# Battery-Management.net
KiCad netlist of a schematic drawn in Altium Designer
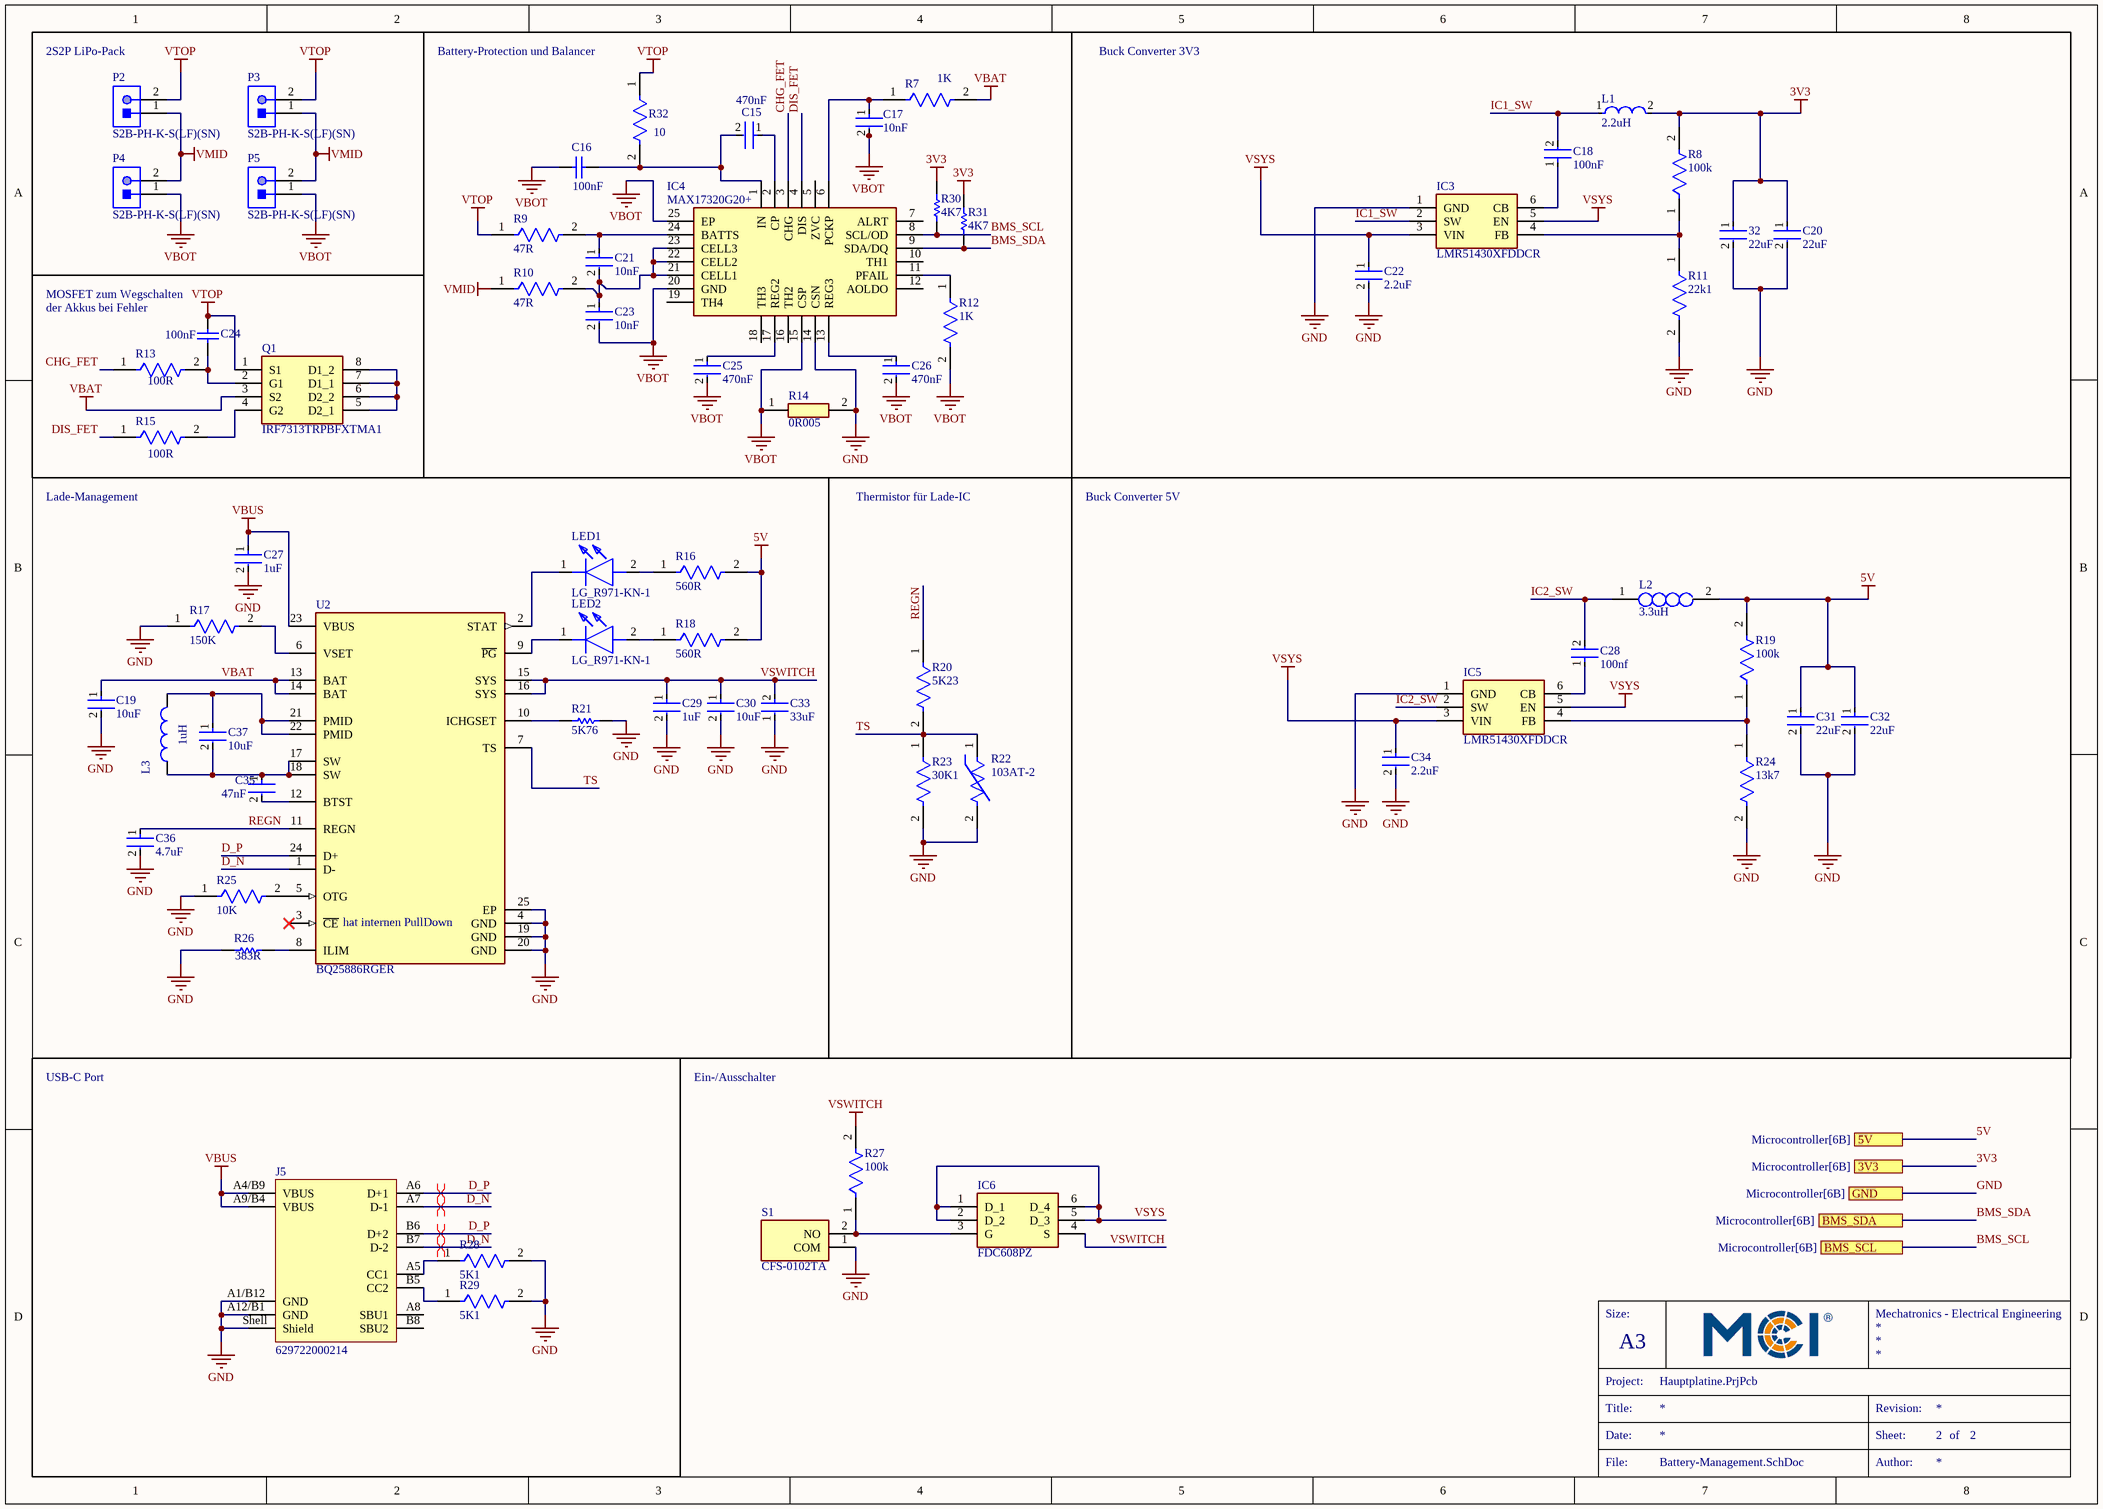
[diagram p0: Battery-Management.SchDoc]

(export (version "E")
  (design (tool "Eeschema 10.0.6"))
  (components
    (comp (ref "32")
      (value "22uF")
      (footprint "FP-C1210C226K4RACTU-MFG")
      (description "CAP CER 22UF 16V X7R 1210")
      (fields (field (name "VOLTAGE") "16V") (field (name "TOLERANCE") "10%"))
      (libsource (lib "Altium Content Vault") (part "b4654b650e69147ec39a6b967a45e02"))
    )
    (comp (ref "C15")
      (value "470nF")
      (footprint "FP-C0805C-DN-MFG")
      (description "CAP CER 0.47UF 25V X7R 0805")
      (fields (field (name "MANUFACTURER") "KEMET") (field (name "TOLERANCE") "0.05"))
      (libsource (lib "Altium Content Vault") (part "b4654b650e69147ec39a6b967a45e02"))
    )
    (comp (ref "C16")
      (value "100nF")
      (footprint "CAPC2013X145X50LL20T20")
      (fields (field (name "PART NUMBER") "VJ0805Y104JXXPW1BC") (field (name "MANUFACTURER") "Vitramon"))
      (libsource (lib "Altium Content Vault") (part "CAP"))
    )
    (comp (ref "C17")
      (value "10nF")
      (footprint "FP-AC0805-0_85-MFG")
      (description "AC Series 0805 10 nF 100 V ±10% X7R Multilayer Ceramic Capacitor")
      (fields
        (field (name "MANUFACTURER") "Yageo")
        (field (name "OCTOPART") "https://octopart.com/ac0805krx7r0bb103-yageo-75656636")
      )
      (libsource (lib "Altium Content Vault") (part "11868f565c42a9108669ba33697ecf6"))
    )
    (comp (ref "C18")
      (value "100nF")
      (footprint "FP-C0805C104M5UACTU-MFG")
      (description "CAP CER 0.1UF 50V Z5U 0805")
      (fields (field (name "TOLERANCE") "20%") (field (name "VOLTAGE") "50V"))
      (libsource (lib "Altium Content Vault") (part "b4654b650e69147ec39a6b967a45e02"))
    )
    (comp (ref "C19")
      (value "10uF")
      (footprint "FP-GRM21B-0_15-IPC_A")
      (description "Chip Multilayer Ceramic Capacitors for General Purpose, 0805, 10uF, X5R, 15%, 20%, 25V")
      (fields (field (name "TOLERANCE") "20%"))
      (libsource (lib "Altium Content Vault") (part "b4654b650e69147ec39a6b967a45e02"))
    )
    (comp (ref "C20")
      (value "22uF")
      (footprint "FP-C1210C226K4RACTU-MFG")
      (description "CAP CER 22UF 16V X7R 1210")
      (fields (field (name "VOLTAGE") "16V") (field (name "TOLERANCE") "10%"))
      (libsource (lib "Altium Content Vault") (part "b4654b650e69147ec39a6b967a45e02"))
    )
    (comp (ref "C21")
      (value "10nF")
      (footprint "FP-AC0805-0_85-MFG")
      (description "AC Series 0805 10 nF 100 V ±10% X7R Multilayer Ceramic Capacitor")
      (fields
        (field (name "MANUFACTURER") "Yageo")
        (field (name "OCTOPART") "https://octopart.com/ac0805krx7r0bb103-yageo-75656636")
      )
      (libsource (lib "Altium Content Vault") (part "11868f565c42a9108669ba33697ecf6"))
    )
    (comp (ref "C22")
      (value "2.2uF")
      (footprint "FP-CC1210-G3-MFG")
      (description "CAP CER 1210")
      (fields (field (name "TOLERANCE") "10%"))
      (libsource (lib "Altium Content Vault") (part "b4654b650e69147ec39a6b967a45e02"))
    )
    (comp (ref "C23")
      (value "10nF")
      (footprint "FP-AC0805-0_85-MFG")
      (description "AC Series 0805 10 nF 100 V ±10% X7R Multilayer Ceramic Capacitor")
      (fields
        (field (name "MANUFACTURER") "Yageo")
        (field (name "OCTOPART") "https://octopart.com/ac0805krx7r0bb103-yageo-75656636")
      )
      (libsource (lib "Altium Content Vault") (part "11868f565c42a9108669ba33697ecf6"))
    )
    (comp (ref "C24")
      (value "100nF")
      (footprint "CAPC2013X145X50LL20T20")
      (fields (field (name "PART NUMBER") "VJ0805Y104JXXPW1BC") (field (name "MANUFACTURER") "Vitramon"))
      (libsource (lib "Altium Content Vault") (part "CAP"))
    )
    (comp (ref "C25")
      (value "470nF")
      (footprint "FP-C0805C-DN-MFG")
      (description "CAP CER 0.47UF 25V X7R 0805")
      (fields (field (name "MANUFACTURER") "KEMET") (field (name "TOLERANCE") "0.05"))
      (libsource (lib "Altium Content Vault") (part "b4654b650e69147ec39a6b967a45e02"))
    )
    (comp (ref "C26")
      (value "470nF")
      (footprint "FP-C0805C-DN-MFG")
      (description "CAP CER 0.47UF 25V X7R 0805")
      (fields (field (name "MANUFACTURER") "KEMET") (field (name "TOLERANCE") "0.05"))
      (libsource (lib "Altium Content Vault") (part "b4654b650e69147ec39a6b967a45e02"))
    )
    (comp (ref "C27")
      (value "1uF")
      (footprint "FP-CGA4J-MFG")
      (description "Cap Ceramic 1uF 16V X7R 10% Pad SMD 0805 +125°C Automotive T/R")
      (fields (field (name "TOLERANCE") "10%"))
      (libsource (lib "Altium Content Vault") (part "b4654b650e69147ec39a6b967a45e02"))
    )
    (comp (ref "C28")
      (value "100nf")
      (footprint "FP-C0805C104M5UACTU-MFG")
      (description "CAP CER 0.1UF 50V Z5U 0805")
      (fields (field (name "TOLERANCE") "20%") (field (name "VOLTAGE") "50V"))
      (libsource (lib "Altium Content Vault") (part "b4654b650e69147ec39a6b967a45e02"))
    )
    (comp (ref "C29")
      (value "1uF")
      (footprint "FP-CGA4J-MFG")
      (description "Cap Ceramic 1uF 16V X7R 10% Pad SMD 0805 +125°C Automotive T/R")
      (fields (field (name "TOLERANCE") "10%"))
      (libsource (lib "Altium Content Vault") (part "b4654b650e69147ec39a6b967a45e02"))
    )
    (comp (ref "C30")
      (value "10uF")
      (footprint "FP-C0805C-DG-MFG")
      (description "SMD Comm X5R, Ceramic, 10 uF, 10%, 10 V, X5R, SMD, MLCC, Temperature Stable, Class II, 0805")
      (fields (field (name "TOLERANCE") "10%"))
      (libsource (lib "Altium Content Vault") (part "11868f565c42a9108669ba33697ecf6"))
    )
    (comp (ref "C31")
      (value "22uF")
      (footprint "FP-C1210C226K4RACTU-MFG")
      (description "CAP CER 22UF 16V X7R 1210")
      (fields (field (name "VOLTAGE") "16V") (field (name "TOLERANCE") "10%"))
      (libsource (lib "Altium Content Vault") (part "b4654b650e69147ec39a6b967a45e02"))
    )
    (comp (ref "C32")
      (value "22uF")
      (footprint "FP-C1210C226K4RACTU-MFG")
      (description "CAP CER 22UF 16V X7R 1210")
      (fields (field (name "VOLTAGE") "16V") (field (name "TOLERANCE") "10%"))
      (libsource (lib "Altium Content Vault") (part "b4654b650e69147ec39a6b967a45e02"))
    )
    (comp (ref "C33")
      (value "33uF")
      (footprint "FP-KRM55Q-6_1_5_3_3_9_1_2-MFG")
      (description "Cap Ceramic 33uF 25V X7R ±10% SMD 2220 +125°C Emboss T/R")
      (libsource (lib "Altium Content Vault") (part "f23184f103b6ebe33a8c269c53dcba6"))
    )
    (comp (ref "C34")
      (value "2.2uF")
      (footprint "FP-CC1210-G3-MFG")
      (description "CAP CER 1210")
      (fields (field (name "TOLERANCE") "10%"))
      (libsource (lib "Altium Content Vault") (part "b4654b650e69147ec39a6b967a45e02"))
    )
    (comp (ref "C35")
      (value "47nF")
      (footprint "FP-C1206C-EB-MFG")
      (description "CAP CER 0.047UF 50V X8R 1206")
      (fields
        (field (name "MANUFACTURER") "KEMET")
        (field (name "MANUFACTURER PART NUMBER") "C1206C473K5HACTU")
      )
      (libsource (lib "Altium Content Vault") (part "b4654b650e69147ec39a6b967a45e02"))
    )
    (comp (ref "C36")
      (value "4.7uF")
      (footprint "FP-C0805C475K3RACAUTO-MFG")
      (description "CAP CER 0805 4.7UF 25V X7R  10%")
      (libsource (lib "Altium Content Vault") (part "b4654b650e69147ec39a6b967a45e02"))
    )
    (comp (ref "C37")
      (value "10uF")
      (footprint "FP-GRM21B-0_15-IPC_A")
      (description "Chip Multilayer Ceramic Capacitors for General Purpose, 0805, 10uF, X5R, 15%, 20%, 25V")
      (fields (field (name "TOLERANCE") "20%"))
      (libsource (lib "Altium Content Vault") (part "b4654b650e69147ec39a6b967a45e02"))
    )
    (comp (ref "IC3")
      (value "LMR51430XFDDCR")
      (footprint "SamacSys:SOT95P280X110-6N")
      (description "Integrated Circuit")
      (fields (field (name "MOUSER PART NUMBER") "595-LMR51430XFDDCR"))
      (libsource (lib "*") (part "LMR51430XFDDCR"))
    )
    (comp (ref "IC4")
      (value "MAX17320G20+")
      (footprint "Library:QFN50P400X400X80-25N")
      (description "Integrated Circuit")
      (fields (field (name "MOUSER PART NUMBER") "700-MAX17320G20+"))
      (libsource (lib "*") (part "MAX17320G20+"))
    )
    (comp (ref "IC5")
      (value "LMR51430XFDDCR")
      (footprint "SamacSys:SOT95P280X110-6N")
      (description "Integrated Circuit")
      (fields (field (name "MOUSER PART NUMBER") "595-LMR51430XFDDCR"))
      (libsource (lib "*") (part "LMR51430XFDDCR"))
    )
    (comp (ref "IC6")
      (value "FDC608PZ")
      (footprint "Library:SOT95P275X110-6N")
      (description "Integrated Circuit")
      (fields (field (name "MOUSER PART NUMBER") "512-FDC608PZ"))
      (libsource (lib "*") (part "FDC608PZ"))
    )
    (comp (ref "J5")
      (value "629722000214")
      (footprint "629722000214")
      (description "Usb Conn, R/a, Type C 2.0, Rcpt, 16POS Rohs Compliant: Yes")
      (libsource (lib "Altium Content Vault") (part "USB 2.0_Type C_Receptacle_1 Port_629722000214"))
    )
    (comp (ref "L1")
      (value "2.2uH")
      (footprint "FP-IHLP-2020BZ-FP_1_905x2-MFG")
      (description "Fixed Inductors Commercial Low DCR Series 2.2uH 5A 37.7mΩ 20%")
      (fields (field (name "TOLERANCE") "20%"))
      (libsource (lib "Altium Content Vault") (part "725321dda6339637d4d059423bc1c3c"))
    )
    (comp (ref "L2")
      (value "3.3uH")
      (footprint "SamacSys:INDPM6054X300N")
      (description "Inductor")
      (fields
        (field (name "MANUFACTURER_PART_NUMBER") "PA4340.332NLT")
        (field (name "MOUSER PART NUMBER") "673-PA4340.332NLT")
      )
      (libsource (lib "*") (part "PA4340.332NLT"))
    )
    (comp (ref "L3")
      (value "1uH")
      (footprint "WE-PMFI_322512")
      (description "Power Ind, 1UH, 5.8A, Shielded, 1210 Rohs Compliant: Yes")
      (libsource (lib "Altium Content Vault") (part "Inductor - 1"))
    )
    (comp (ref "LED1")
      (value "LG_R971-KN-1")
      (footprint "Library:LEDC2012X80N")
      (description "LED")
      (fields
        (field (name "MANUFACTURER_PART_NUMBER") "LG R971-KN-1")
        (field (name "MOUSER PART NUMBER") "720-LGR971-KN-1")
      )
      (libsource (lib "*") (part "LG_R971-KN-1"))
    )
    (comp (ref "LED2")
      (value "LG_R971-KN-1")
      (footprint "Library:LEDC2012X80N")
      (description "LED")
      (fields
        (field (name "MANUFACTURER_PART_NUMBER") "LG R971-KN-1")
        (field (name "MOUSER PART NUMBER") "720-LGR971-KN-1")
      )
      (libsource (lib "*") (part "LG_R971-KN-1"))
    )
    (comp (ref "P2")
      (value "S2B-PH-K-S(LF)(SN)")
      (footprint "JST-S2B-PH-K-S_V")
      (fields (field (name "TOLERANCE") "20%"))
      (libsource (lib "Altium Content Vault") (part "CN-1P-M-R2"))
    )
    (comp (ref "P3")
      (value "S2B-PH-K-S(LF)(SN)")
      (footprint "JST-S2B-PH-K-S_V")
      (fields (field (name "TOLERANCE") "20%"))
      (libsource (lib "Altium Content Vault") (part "CN-1P-M-R2"))
    )
    (comp (ref "P4")
      (value "S2B-PH-K-S(LF)(SN)")
      (footprint "JST-S2B-PH-K-S_V")
      (fields (field (name "TOLERANCE") "20%"))
      (libsource (lib "Altium Content Vault") (part "CN-1P-M-R2"))
    )
    (comp (ref "P5")
      (value "S2B-PH-K-S(LF)(SN)")
      (footprint "JST-S2B-PH-K-S_V")
      (fields (field (name "TOLERANCE") "20%"))
      (libsource (lib "Altium Content Vault") (part "CN-1P-M-R2"))
    )
    (comp (ref "Q1")
      (value "IRF7313TRPBFXTMA1")
      (footprint "Library:SOIC127P600X175-8N")
      (description "MOSFET (N-Channel)")
      (fields (field (name "MOUSER PART NUMBER") "726-IRF7313TRPBFXTMA"))
      (libsource (lib "*") (part "IRF7313TRPBFXTMA1"))
    )
    (comp (ref "R7")
      (value "1K")
      (footprint "FP-PCAN0805-MFG")
      (description "RES SMD 1K OHM 0.1% 1W 0805")
      (fields (field (name "TOLERANCE") "0.1%") (field (name "MANUFACTURER PART NUMBER") "PCAN0805E1001BST5"))
      (libsource (lib "Altium Content Vault") (part "1029c3af85768c4190bb7ad29bc67b5"))
    )
    (comp (ref "R8")
      (value "100k")
      (footprint "FP-RQ73C2A-IPC_B")
      (description "RQ73 0805 100KΩ 0.2W 10ppm/°C 0.1% 100V")
      (libsource (lib "Altium Content Vault") (part "1029c3af85768c4190bb7ad29bc67b5"))
    )
    (comp (ref "R9")
      (value "47R")
      (footprint "FP-CRGP1206-IPC_C")
      (description "CRGP1206 47Ω 0.5W ±100ppm/°C 1% 200V")
      (fields (field (name "TOLERANCE") "0.01") (field (name "MANUFACTURER PART NUMBER") "CRGP1206F47R"))
      (libsource (lib "Altium Content Vault") (part "1029c3af85768c4190bb7ad29bc67b5"))
    )
    (comp (ref "R10")
      (value "47R")
      (footprint "FP-CRGP1206-IPC_C")
      (description "CRGP1206 47Ω 0.5W ±100ppm/°C 1% 200V")
      (fields (field (name "TOLERANCE") "0.01") (field (name "MANUFACTURER PART NUMBER") "CRGP1206F47R"))
      (libsource (lib "Altium Content Vault") (part "1029c3af85768c4190bb7ad29bc67b5"))
    )
    (comp (ref "R11")
      (value "22k1")
      (footprint "FP-RT0805-MFG")
      (description "RES SMD 22.1K OHM 0.1% 1/8W 0805")
      (fields
        (field (name "MANUFACTURER PART NUMBER") "RT0805BRD0722K1L")
        (field (name "MANUFACTURER") "Yageo")
      )
      (libsource (lib "Altium Content Vault") (part "1029c3af85768c4190bb7ad29bc67b5"))
    )
    (comp (ref "R12")
      (value "1K")
      (footprint "FP-PCAN0805-MFG")
      (description "RES SMD 1K OHM 0.1% 1W 0805")
      (fields (field (name "TOLERANCE") "0.1%") (field (name "MANUFACTURER PART NUMBER") "PCAN0805E1001BST5"))
      (libsource (lib "Altium Content Vault") (part "1029c3af85768c4190bb7ad29bc67b5"))
    )
    (comp (ref "R13")
      (value "100R")
      (footprint "FP-RN73R2A-IPC_A")
      (description "100Ω ±0.1% 0.125W, 1/8W Chip Resistor 0805 (2012 Metric) Moisture Resistant Thin Film")
      (libsource (lib "Altium Content Vault") (part "1029c3af85768c4190bb7ad29bc67b5"))
    )
    (comp (ref "R14")
      (value "0R005")
      (footprint "Library:RESC7146X175N")
      (description "Resistor")
      (fields
        (field (name "MANUFACTURER_PART_NUMBER") "WSHP28185L000FEA")
        (field (name "MOUSER PART NUMBER") "71-WSHP28185L000FEA")
      )
      (libsource (lib "*") (part "WSHP28185L000FEA"))
    )
    (comp (ref "R15")
      (value "100R")
      (footprint "FP-RN73R2A-IPC_A")
      (description "100Ω ±0.1% 0.125W, 1/8W Chip Resistor 0805 (2012 Metric) Moisture Resistant Thin Film")
      (libsource (lib "Altium Content Vault") (part "1029c3af85768c4190bb7ad29bc67b5"))
    )
    (comp (ref "R16")
      (value "560R")
      (footprint "FP-RMCF0805-IPC_A")
      (description "560Ω ±5% 0.125W 0805 Thick Film Chip Resistor AEC-Q200 compliant")
      (fields (field (name "TOLERANCE") "5%"))
      (libsource (lib "Altium Content Vault") (part "1029c3af85768c4190bb7ad29bc67b5"))
    )
    (comp (ref "R17")
      (value "150K")
      (footprint "FP-RK73H2A-IPC_B")
      (description "150kΩ ±1% 0.25W Chip Resistor 0805 Thick Film AEC-Q200 Qualified")
      (fields (field (name "TOLERANCE") "1%"))
      (libsource (lib "Altium Content Vault") (part "1029c3af85768c4190bb7ad29bc67b5"))
    )
    (comp (ref "R18")
      (value "560R")
      (footprint "FP-RMCF0805-IPC_A")
      (description "560Ω ±5% 0.125W 0805 Thick Film Chip Resistor AEC-Q200 compliant")
      (fields (field (name "TOLERANCE") "5%"))
      (libsource (lib "Altium Content Vault") (part "1029c3af85768c4190bb7ad29bc67b5"))
    )
    (comp (ref "R19")
      (value "100k")
      (footprint "FP-RQ73C2A-IPC_B")
      (description "RQ73 0805 100KΩ 0.2W 10ppm/°C 0.1% 100V")
      (libsource (lib "Altium Content Vault") (part "1029c3af85768c4190bb7ad29bc67b5"))
    )
    (comp (ref "R20")
      (value "5K23")
      (footprint "FP-RP73P-2A-MFG")
      (description "RP73P 0805 5.23KΩ 0.25W 25ppm/°C 0.10% 150V")
      (fields (field (name "MANUFACTURER") "TE Connectivity") (field (name "TOLERANCE") "0.001"))
      (libsource (lib "Altium Content Vault") (part "1029c3af85768c4190bb7ad29bc67b5"))
    )
    (comp (ref "R21")
      (value "5K76")
      (footprint "RESC2013X60X35ML10T20")
      (fields (field (name "PART NUMBER") "RC0805FR-075K76L") (field (name "MANUFACTURER") "Yageo"))
      (libsource (lib "Altium Content Vault") (part "RES"))
    )
    (comp (ref "R22")
      (value "103AT-2")
      (footprint "FP-103AT-2-MFG")
      (description "Thermistor NTC 10KOhm 1% 2-Pin")
      (fields (field (name "TOLERANCE") "1%"))
      (libsource (lib "Altium Content Vault") (part "3b148a6ebabc5fb4d708a66c052d352"))
    )
    (comp (ref "R23")
      (value "30K1")
      (footprint "FP-MCU0805-IPC_C")
      (description "RES 1.05K OHM 0.5% 1/5W 0805")
      (fields (field (name "TOLERANCE") "0.1%"))
      (libsource (lib "Altium Content Vault") (part "1029c3af85768c4190bb7ad29bc67b5"))
    )
    (comp (ref "R24")
      (value "13k7")
      (footprint "FP-RT0805-MFG")
      (description "RES 13.7K OHM 1/8W .1% SMD 0805")
      (fields
        (field (name "MANUFACTURER PART NUMBER") "RT0805BRD0713K7L")
        (field (name "MANUFACTURER") "Yageo")
      )
      (libsource (lib "Altium Content Vault") (part "1029c3af85768c4190bb7ad29bc67b5"))
    )
    (comp (ref "R25")
      (value "10K")
      (footprint "FP-AT0805-MFG")
      (description "Thin Film Chip Resistors Automotive Grade 10kΩ 0.5% 50ppm/°C 0805")
      (fields (field (name "TOLERANCE") "0.5%"))
      (libsource (lib "Altium Content Vault") (part "1029c3af85768c4190bb7ad29bc67b5"))
    )
    (comp (ref "R26")
      (value "383R")
      (footprint "RESC2013X60X35LL10T20")
      (fields (field (name "PART NUMBER") "RC0805FR-07383RL") (field (name "MANUFACTURER") "Yageo"))
      (libsource (lib "Altium Content Vault") (part "RES"))
    )
    (comp (ref "R27")
      (value "100k")
      (footprint "FP-RQ73C2A-IPC_B")
      (description "RQ73 0805 100KΩ 0.2W 10ppm/°C 0.1% 100V")
      (libsource (lib "Altium Content Vault") (part "1029c3af85768c4190bb7ad29bc67b5"))
    )
    (comp (ref "R28")
      (value "5K1")
      (footprint "FP-AC0805-MFG")
      (description "RES SMD 5.1K OHM 5% 1/8W 0805")
      (fields
        (field (name "OCTOPART") "https://octopart.com/ac0805jr-075k1l-yageo-21711115")
        (field (name "MANUFACTURER") "Yageo")
      )
      (libsource (lib "Altium Content Vault") (part "1029c3af85768c4190bb7ad29bc67b5"))
    )
    (comp (ref "R29")
      (value "5K1")
      (footprint "FP-AC0805-MFG")
      (description "RES SMD 5.1K OHM 5% 1/8W 0805")
      (fields
        (field (name "OCTOPART") "https://octopart.com/ac0805jr-075k1l-yageo-21711115")
        (field (name "MANUFACTURER") "Yageo")
      )
      (libsource (lib "Altium Content Vault") (part "1029c3af85768c4190bb7ad29bc67b5"))
    )
    (comp (ref "R30")
      (value "4K7")
      (footprint "RESC2013X60X35NL10T20")
      (fields (field (name "MANUFACTURER") "Yageo") (field (name "PART NUMBER") "RC0805JR-134K7L"))
      (libsource (lib "Altium Content Vault") (part "RES"))
    )
    (comp (ref "R31")
      (value "4K7")
      (footprint "RESC2013X60X35NL10T20")
      (fields (field (name "MANUFACTURER") "Yageo") (field (name "PART NUMBER") "RC0805JR-134K7L"))
      (libsource (lib "Altium Content Vault") (part "RES"))
    )
    (comp (ref "R32")
      (value "10")
      (footprint "FP-RT0805-MFG")
      (description "RES SMD 10 OHM 1% 1/8W 0805")
      (fields (field (name "TOLERANCE") "0.0001") (field (name "MANUFACTURER PART NUMBER") "RT0805FRE0710RL"))
      (libsource (lib "Altium Content Vault") (part "1029c3af85768c4190bb7ad29bc67b5"))
    )
    (comp (ref "S1")
      (value "CFS-0102TA")
      (footprint "Library:CFS0102TA")
      (description "Switch")
      (fields (field (name "MOUSER PART NUMBER") "229-CFS-0102TA"))
      (libsource (lib "*") (part "CFS-0102TA"))
    )
    (comp (ref "U2")
      (value "BQ25886RGER")
      (footprint "FP-RGE0024H-IPC_C")
      (description "PWR MGMT BATTERY MGMT")
      (libsource (lib "Altium Content Vault") (part "89915a63032611fcbc02831425e9645"))
    )
  )
  (nets
    (net (code "1") (name "/BMS_SCL") (class "Default")
      (node (ref "IC4") (pin "8") (pinfunction "SCL/OD_8") (pintype "passive"))
      (node (ref "R30") (pin "1") (pinfunction "1_1") (pintype "passive"))
    )
    (net (code "2") (name "/BMS_SDA") (class "Default")
      (node (ref "IC4") (pin "9") (pinfunction "SDA/DQ_9") (pintype "passive"))
      (node (ref "R31") (pin "1") (pinfunction "1_1") (pintype "passive"))
    )
    (net (code "3") (name "/CHG_FET") (class "Default")
      (node (ref "IC4") (pin "3") (pinfunction "CHG_3") (pintype "passive"))
      (node (ref "R13") (pin "1") (pinfunction "1_1") (pintype "passive"))
    )
    (net (code "4") (name "/DIS_FET") (class "Default")
      (node (ref "IC4") (pin "4") (pinfunction "DIS_4") (pintype "passive"))
      (node (ref "R15") (pin "1") (pinfunction "1_1") (pintype "passive"))
    )
    (net (code "5") (name "/D_N") (class "Default")
      (node (ref "J5") (pin "A7") (pinfunction "D-1_A7") (pintype "passive"))
      (node (ref "J5") (pin "B7") (pinfunction "D-2_B7") (pintype "passive"))
      (node (ref "U2") (pin "1") (pinfunction "D-_1") (pintype "passive"))
    )
    (net (code "6") (name "/D_P") (class "Default")
      (node (ref "J5") (pin "A6") (pinfunction "D+1_A6") (pintype "passive"))
      (node (ref "J5") (pin "B6") (pinfunction "D+2_B6") (pintype "passive"))
      (node (ref "U2") (pin "24") (pinfunction "D+_24") (pintype "passive"))
    )
    (net (code "7") (name "/IC1_SW") (class "Default")
      (node (ref "C18") (pin "2") (pinfunction "2_2") (pintype "passive"))
      (node (ref "IC3") (pin "2") (pinfunction "SW_2") (pintype "passive"))
      (node (ref "L1") (pin "1") (pinfunction "1_1") (pintype "passive"))
    )
    (net (code "8") (name "/IC2_SW") (class "Default")
      (node (ref "C28") (pin "2") (pinfunction "2_2") (pintype "passive"))
      (node (ref "IC5") (pin "2") (pinfunction "SW_2") (pintype "passive"))
      (node (ref "L2") (pin "1") (pinfunction "1_1") (pintype "passive"))
    )
    (net (code "9") (name "/REGN") (class "Default")
      (node (ref "C36") (pin "1") (pinfunction "1_1") (pintype "passive"))
      (node (ref "R20") (pin "1") (pinfunction "1_1") (pintype "passive"))
      (node (ref "U2") (pin "11") (pinfunction "REGN_11") (pintype "power_in"))
    )
    (net (code "10") (name "/TS") (class "Default")
      (node (ref "R20") (pin "2") (pinfunction "2_2") (pintype "passive"))
      (node (ref "R22") (pin "1") (pinfunction "1_1") (pintype "passive"))
      (node (ref "R23") (pin "1") (pinfunction "1_1") (pintype "passive"))
      (node (ref "U2") (pin "7") (pinfunction "TS_7") (pintype "passive"))
    )
    (net (code "11") (name "3V3") (class "Default")
      (node (ref "32") (pin "1") (pinfunction "1_1") (pintype "passive"))
      (node (ref "C20") (pin "1") (pinfunction "1_1") (pintype "passive"))
      (node (ref "L1") (pin "2") (pinfunction "2_2") (pintype "passive"))
      (node (ref "R30") (pin "2") (pinfunction "2_2") (pintype "passive"))
      (node (ref "R31") (pin "2") (pinfunction "2_2") (pintype "passive"))
      (node (ref "R8") (pin "2") (pinfunction "2_2") (pintype "passive"))
    )
    (net (code "12") (name "5V") (class "Default")
      (node (ref "C31") (pin "1") (pinfunction "1_1") (pintype "passive"))
      (node (ref "C32") (pin "1") (pinfunction "1_1") (pintype "passive"))
      (node (ref "L2") (pin "2") (pinfunction "2_2") (pintype "passive"))
      (node (ref "R16") (pin "2") (pinfunction "2_2") (pintype "passive"))
      (node (ref "R18") (pin "2") (pinfunction "2_2") (pintype "passive"))
      (node (ref "R19") (pin "2") (pinfunction "2_2") (pintype "passive"))
    )
    (net (code "13") (name "GND") (class "Default")
      (node (ref "32") (pin "2") (pinfunction "2_2") (pintype "passive"))
      (node (ref "C19") (pin "2") (pinfunction "2_2") (pintype "passive"))
      (node (ref "C20") (pin "2") (pinfunction "2_2") (pintype "passive"))
      (node (ref "C22") (pin "2") (pinfunction "2_2") (pintype "passive"))
      (node (ref "C27") (pin "2") (pinfunction "2_2") (pintype "passive"))
      (node (ref "C29") (pin "2") (pinfunction "2_2") (pintype "passive"))
      (node (ref "C30") (pin "2") (pinfunction "2_2") (pintype "passive"))
      (node (ref "C31") (pin "2") (pinfunction "2_2") (pintype "passive"))
      (node (ref "C32") (pin "2") (pinfunction "2_2") (pintype "passive"))
      (node (ref "C33") (pin "1") (pinfunction "1_1") (pintype "passive"))
      (node (ref "C34") (pin "2") (pinfunction "2_2") (pintype "passive"))
      (node (ref "C36") (pin "2") (pinfunction "2_2") (pintype "passive"))
      (node (ref "IC3") (pin "1") (pinfunction "GND_1") (pintype "passive"))
      (node (ref "IC4") (pin "14") (pinfunction "CSN_14") (pintype "passive"))
      (node (ref "IC5") (pin "1") (pinfunction "GND_1") (pintype "passive"))
      (node (ref "J5") (pin "A1/B12") (pinfunction "GND_A1/B12") (pintype "passive"))
      (node (ref "J5") (pin "A12/B1") (pinfunction "GND_A12/B1") (pintype "passive"))
      (node (ref "J5") (pin "Shell") (pinfunction "Shield_Shell") (pintype "passive"))
      (node (ref "R11") (pin "2") (pinfunction "2_2") (pintype "passive"))
      (node (ref "R14") (pin "2") (pinfunction "2_2") (pintype "passive"))
      (node (ref "R17") (pin "1") (pinfunction "1_1") (pintype "passive"))
      (node (ref "R21") (pin "2") (pinfunction "2_2") (pintype "passive"))
      (node (ref "R22") (pin "2") (pinfunction "2_2") (pintype "passive"))
      (node (ref "R23") (pin "2") (pinfunction "2_2") (pintype "passive"))
      (node (ref "R24") (pin "2") (pinfunction "2_2") (pintype "passive"))
      (node (ref "R25") (pin "1") (pinfunction "1_1") (pintype "passive"))
      (node (ref "R26") (pin "1") (pinfunction "1_1") (pintype "passive"))
      (node (ref "R28") (pin "2") (pinfunction "2_2") (pintype "passive"))
      (node (ref "R29") (pin "2") (pinfunction "2_2") (pintype "passive"))
      (node (ref "S1") (pin "1") (pinfunction "COM_1") (pintype "passive"))
      (node (ref "U2") (pin "19") (pinfunction "GND_19") (pintype "power_in"))
      (node (ref "U2") (pin "20") (pinfunction "GND_20") (pintype "power_in"))
      (node (ref "U2") (pin "25") (pinfunction "EP_25") (pintype "power_in"))
      (node (ref "U2") (pin "4") (pinfunction "GND_4") (pintype "power_in"))
    )
    (net (code "14") (name "Net-(C35-Pad1)") (class "Default")
      (node (ref "C35") (pin "1") (pinfunction "1_1") (pintype "passive"))
      (node (ref "C37") (pin "2") (pinfunction "2_2") (pintype "passive"))
      (node (ref "L3") (pin "1") (pinfunction "1_1") (pintype "passive"))
      (node (ref "U2") (pin "17") (pinfunction "SW_17") (pintype "power_in"))
      (node (ref "U2") (pin "18") (pinfunction "SW_18") (pintype "power_in"))
    )
    (net (code "15") (name "Net-(C37-Pad1)") (class "Default")
      (node (ref "C37") (pin "1") (pinfunction "1_1") (pintype "passive"))
      (node (ref "L3") (pin "2") (pinfunction "2_2") (pintype "passive"))
      (node (ref "U2") (pin "21") (pinfunction "PMID_21") (pintype "power_in"))
      (node (ref "U2") (pin "22") (pinfunction "PMID_22") (pintype "power_in"))
    )
    (net (code "16") (name "Net-(IC3-CB)") (class "Default")
      (node (ref "C18") (pin "1") (pinfunction "1_1") (pintype "passive"))
      (node (ref "IC3") (pin "6") (pinfunction "CB_6") (pintype "passive"))
    )
    (net (code "17") (name "Net-(IC3-FB)") (class "Default")
      (node (ref "IC3") (pin "4") (pinfunction "FB_4") (pintype "passive"))
      (node (ref "R11") (pin "1") (pinfunction "1_1") (pintype "passive"))
      (node (ref "R8") (pin "1") (pinfunction "1_1") (pintype "passive"))
    )
    (net (code "18") (name "Net-(IC4-BATTS)") (class "Default")
      (node (ref "C21") (pin "1") (pinfunction "1_1") (pintype "passive"))
      (node (ref "IC4") (pin "24") (pinfunction "BATTS_24") (pintype "passive"))
      (node (ref "R9") (pin "2") (pinfunction "2_2") (pintype "passive"))
    )
    (net (code "19") (name "Net-(IC4-CELL1)") (class "Default")
      (node (ref "C21") (pin "2") (pinfunction "2_2") (pintype "passive"))
      (node (ref "C23") (pin "1") (pinfunction "1_1") (pintype "passive"))
      (node (ref "IC4") (pin "21") (pinfunction "CELL1_21") (pintype "passive"))
      (node (ref "IC4") (pin "22") (pinfunction "CELL2_22") (pintype "passive"))
      (node (ref "IC4") (pin "23") (pinfunction "CELL3_23") (pintype "passive"))
      (node (ref "R10") (pin "2") (pinfunction "2_2") (pintype "passive"))
    )
    (net (code "20") (name "Net-(IC4-CP)") (class "Default")
      (node (ref "C15") (pin "1") (pinfunction "1_1") (pintype "passive"))
      (node (ref "IC4") (pin "2") (pinfunction "CP_2") (pintype "passive"))
    )
    (net (code "21") (name "Net-(IC4-IN)") (class "Default")
      (node (ref "C15") (pin "2") (pinfunction "2_2") (pintype "passive"))
      (node (ref "C16") (pin "2") (pinfunction "2_2") (pintype "passive"))
      (node (ref "IC4") (pin "1") (pinfunction "IN_1") (pintype "passive"))
      (node (ref "R32") (pin "2") (pinfunction "2_2") (pintype "passive"))
    )
    (net (code "22") (name "Net-(IC4-PCKP)") (class "Default")
      (node (ref "C17") (pin "1") (pinfunction "1_1") (pintype "passive"))
      (node (ref "IC4") (pin "6") (pinfunction "PCKP_6") (pintype "passive"))
      (node (ref "R7") (pin "1") (pinfunction "1_1") (pintype "passive"))
    )
    (net (code "23") (name "Net-(IC4-PFAIL)") (class "Default")
      (node (ref "IC4") (pin "11") (pinfunction "PFAIL_11") (pintype "passive"))
      (node (ref "R12") (pin "1") (pinfunction "1_1") (pintype "passive"))
    )
    (net (code "24") (name "Net-(IC4-REG2)") (class "Default")
      (node (ref "C25") (pin "1") (pinfunction "1_1") (pintype "passive"))
      (node (ref "IC4") (pin "17") (pinfunction "REG2_17") (pintype "passive"))
    )
    (net (code "25") (name "Net-(IC4-REG3)") (class "Default")
      (node (ref "C26") (pin "1") (pinfunction "1_1") (pintype "passive"))
      (node (ref "IC4") (pin "13") (pinfunction "REG3_13") (pintype "passive"))
    )
    (net (code "26") (name "Net-(IC5-CB)") (class "Default")
      (node (ref "C28") (pin "1") (pinfunction "1_1") (pintype "passive"))
      (node (ref "IC5") (pin "6") (pinfunction "CB_6") (pintype "passive"))
    )
    (net (code "27") (name "Net-(IC5-FB)") (class "Default")
      (node (ref "IC5") (pin "4") (pinfunction "FB_4") (pintype "passive"))
      (node (ref "R19") (pin "1") (pinfunction "1_1") (pintype "passive"))
      (node (ref "R24") (pin "1") (pinfunction "1_1") (pintype "passive"))
    )
    (net (code "28") (name "Net-(IC6-G)") (class "Default")
      (node (ref "IC6") (pin "3") (pinfunction "G_3") (pintype "passive"))
      (node (ref "R27") (pin "1") (pinfunction "1_1") (pintype "passive"))
      (node (ref "S1") (pin "2") (pinfunction "NO_2") (pintype "passive"))
    )
    (net (code "29") (name "Net-(J5-CC1)") (class "Default")
      (node (ref "J5") (pin "A5") (pinfunction "CC1_A5") (pintype "passive"))
      (node (ref "R28") (pin "1") (pinfunction "1_1") (pintype "passive"))
    )
    (net (code "30") (name "Net-(J5-CC2)") (class "Default")
      (node (ref "J5") (pin "B5") (pinfunction "CC2_B5") (pintype "passive"))
      (node (ref "R29") (pin "1") (pinfunction "1_1") (pintype "passive"))
    )
    (net (code "31") (name "Net-(LED1-A)") (class "Default")
      (node (ref "LED1") (pin "2") (pinfunction "A_2") (pintype "passive"))
      (node (ref "R16") (pin "1") (pinfunction "1_1") (pintype "passive"))
    )
    (net (code "32") (name "Net-(LED1-K)") (class "Default")
      (node (ref "LED1") (pin "1") (pinfunction "K_1") (pintype "passive"))
      (node (ref "U2") (pin "2") (pinfunction "STAT_2") (pintype "output"))
    )
    (net (code "33") (name "Net-(LED2-A)") (class "Default")
      (node (ref "LED2") (pin "2") (pinfunction "A_2") (pintype "passive"))
      (node (ref "R18") (pin "1") (pinfunction "1_1") (pintype "passive"))
    )
    (net (code "34") (name "Net-(LED2-K)") (class "Default")
      (node (ref "LED2") (pin "1") (pinfunction "K_1") (pintype "passive"))
      (node (ref "U2") (pin "9") (pinfunction "~{PG}_9") (pintype "open_collector"))
    )
    (net (code "35") (name "Net-(Q1-D1_1)") (class "Default")
      (node (ref "Q1") (pin "5") (pinfunction "D2_1_5") (pintype "passive"))
      (node (ref "Q1") (pin "6") (pinfunction "D2_2_6") (pintype "passive"))
      (node (ref "Q1") (pin "7") (pinfunction "D1_1_7") (pintype "passive"))
      (node (ref "Q1") (pin "8") (pinfunction "D1_2_8") (pintype "passive"))
    )
    (net (code "36") (name "Net-(Q1-G1)") (class "Default")
      (node (ref "C24") (pin "1") (pinfunction "1_1") (pintype "passive"))
      (node (ref "Q1") (pin "2") (pinfunction "G1_2") (pintype "passive"))
      (node (ref "R13") (pin "2") (pinfunction "2_2") (pintype "passive"))
    )
    (net (code "37") (name "Net-(Q1-G2)") (class "Default")
      (node (ref "Q1") (pin "4") (pinfunction "G2_4") (pintype "passive"))
      (node (ref "R15") (pin "2") (pinfunction "2_2") (pintype "passive"))
    )
    (net (code "38") (name "Net-(U2-BTST)") (class "Default")
      (node (ref "C35") (pin "2") (pinfunction "2_2") (pintype "passive"))
      (node (ref "U2") (pin "12") (pinfunction "BTST_12") (pintype "power_in"))
    )
    (net (code "39") (name "Net-(U2-ICHGSET)") (class "Default")
      (node (ref "R21") (pin "1") (pinfunction "1_1") (pintype "passive"))
      (node (ref "U2") (pin "10") (pinfunction "ICHGSET_10") (pintype "passive"))
    )
    (net (code "40") (name "Net-(U2-ILIM)") (class "Default")
      (node (ref "R26") (pin "2") (pinfunction "2_2") (pintype "passive"))
      (node (ref "U2") (pin "8") (pinfunction "ILIM_8") (pintype "passive"))
    )
    (net (code "41") (name "Net-(U2-OTG)") (class "Default")
      (node (ref "R25") (pin "2") (pinfunction "2_2") (pintype "passive"))
      (node (ref "U2") (pin "5") (pinfunction "OTG_5") (pintype "input"))
    )
    (net (code "42") (name "Net-(U2-VSET)") (class "Default")
      (node (ref "R17") (pin "2") (pinfunction "2_2") (pintype "passive"))
      (node (ref "U2") (pin "6") (pinfunction "VSET_6") (pintype "passive"))
    )
    (net (code "43") (name "VBAT") (class "Default")
      (node (ref "C19") (pin "1") (pinfunction "1_1") (pintype "passive"))
      (node (ref "Q1") (pin "3") (pinfunction "S2_3") (pintype "passive"))
      (node (ref "R7") (pin "2") (pinfunction "2_2") (pintype "passive"))
      (node (ref "U2") (pin "13") (pinfunction "BAT_13") (pintype "power_in"))
      (node (ref "U2") (pin "14") (pinfunction "BAT_14") (pintype "power_in"))
    )
    (net (code "44") (name "VBOT") (class "Default")
      (node (ref "C16") (pin "1") (pinfunction "1_1") (pintype "passive"))
      (node (ref "C17") (pin "2") (pinfunction "2_2") (pintype "passive"))
      (node (ref "C23") (pin "2") (pinfunction "2_2") (pintype "passive"))
      (node (ref "C25") (pin "2") (pinfunction "2_2") (pintype "passive"))
      (node (ref "C26") (pin "2") (pinfunction "2_2") (pintype "passive"))
      (node (ref "IC4") (pin "15") (pinfunction "CSP_15") (pintype "passive"))
      (node (ref "IC4") (pin "20") (pinfunction "GND_20") (pintype "passive"))
      (node (ref "IC4") (pin "25") (pinfunction "EP_25") (pintype "passive"))
      (node (ref "P4") (pin "1") (pinfunction "1_1") (pintype "passive"))
      (node (ref "P5") (pin "1") (pinfunction "1_1") (pintype "passive"))
      (node (ref "R12") (pin "2") (pinfunction "2_2") (pintype "passive"))
      (node (ref "R14") (pin "1") (pinfunction "1_1") (pintype "passive"))
    )
    (net (code "45") (name "VBUS") (class "Default")
      (node (ref "C27") (pin "1") (pinfunction "1_1") (pintype "passive"))
      (node (ref "J5") (pin "A4/B9") (pinfunction "VBUS_A4/B9") (pintype "passive"))
      (node (ref "J5") (pin "A9/B4") (pinfunction "VBUS_A9/B4") (pintype "passive"))
      (node (ref "U2") (pin "23") (pinfunction "VBUS_23") (pintype "power_in"))
    )
    (net (code "46") (name "VMID") (class "Default")
      (node (ref "P2") (pin "1") (pinfunction "1_1") (pintype "passive"))
      (node (ref "P3") (pin "1") (pinfunction "1_1") (pintype "passive"))
      (node (ref "P4") (pin "2") (pinfunction "2_2") (pintype "passive"))
      (node (ref "P5") (pin "2") (pinfunction "2_2") (pintype "passive"))
      (node (ref "R10") (pin "1") (pinfunction "1_1") (pintype "passive"))
    )
    (net (code "47") (name "VSWITCH") (class "Default")
      (node (ref "C29") (pin "1") (pinfunction "1_1") (pintype "passive"))
      (node (ref "C30") (pin "1") (pinfunction "1_1") (pintype "passive"))
      (node (ref "C33") (pin "2") (pinfunction "2_2") (pintype "passive"))
      (node (ref "IC6") (pin "4") (pinfunction "S_4") (pintype "passive"))
      (node (ref "R27") (pin "2") (pinfunction "2_2") (pintype "passive"))
      (node (ref "U2") (pin "15") (pinfunction "SYS_15") (pintype "power_in"))
      (node (ref "U2") (pin "16") (pinfunction "SYS_16") (pintype "power_in"))
    )
    (net (code "48") (name "VSYS") (class "Default")
      (node (ref "C22") (pin "1") (pinfunction "1_1") (pintype "passive"))
      (node (ref "C34") (pin "1") (pinfunction "1_1") (pintype "passive"))
      (node (ref "IC3") (pin "3") (pinfunction "VIN_3") (pintype "passive"))
      (node (ref "IC3") (pin "5") (pinfunction "EN_5") (pintype "passive"))
      (node (ref "IC5") (pin "3") (pinfunction "VIN_3") (pintype "passive"))
      (node (ref "IC5") (pin "5") (pinfunction "EN_5") (pintype "passive"))
      (node (ref "IC6") (pin "1") (pinfunction "D_1_1") (pintype "passive"))
      (node (ref "IC6") (pin "2") (pinfunction "D_2_2") (pintype "passive"))
      (node (ref "IC6") (pin "5") (pinfunction "D_3_5") (pintype "passive"))
      (node (ref "IC6") (pin "6") (pinfunction "D_4_6") (pintype "passive"))
    )
    (net (code "49") (name "VTOP") (class "Default")
      (node (ref "C24") (pin "2") (pinfunction "2_2") (pintype "passive"))
      (node (ref "P2") (pin "2") (pinfunction "2_2") (pintype "passive"))
      (node (ref "P3") (pin "2") (pinfunction "2_2") (pintype "passive"))
      (node (ref "Q1") (pin "1") (pinfunction "S1_1") (pintype "passive"))
      (node (ref "R32") (pin "1") (pinfunction "1_1") (pintype "passive"))
      (node (ref "R9") (pin "1") (pinfunction "1_1") (pintype "passive"))
    )
    (net (code "50") (name "unconnected-(IC4-ALRT-Pad7)") (class "Default")
      (node (ref "IC4") (pin "7") (pinfunction "ALRT_7") (pintype "passive"))
    )
    (net (code "51") (name "unconnected-(IC4-AOLDO-Pad12)") (class "Default")
      (node (ref "IC4") (pin "12") (pinfunction "AOLDO_12") (pintype "passive"))
    )
    (net (code "52") (name "unconnected-(IC4-TH1-Pad10)") (class "Default")
      (node (ref "IC4") (pin "10") (pinfunction "TH1_10") (pintype "passive"))
    )
    (net (code "53") (name "unconnected-(IC4-TH2-Pad16)") (class "Default")
      (node (ref "IC4") (pin "16") (pinfunction "TH2_16") (pintype "passive"))
    )
    (net (code "54") (name "unconnected-(IC4-TH3-Pad18)") (class "Default")
      (node (ref "IC4") (pin "18") (pinfunction "TH3_18") (pintype "passive"))
    )
    (net (code "55") (name "unconnected-(IC4-TH4-Pad19)") (class "Default")
      (node (ref "IC4") (pin "19") (pinfunction "TH4_19") (pintype "passive"))
    )
    (net (code "56") (name "unconnected-(IC4-ZVC-Pad5)") (class "Default")
      (node (ref "IC4") (pin "5") (pinfunction "ZVC_5") (pintype "passive"))
    )
    (net (code "57") (name "unconnected-(J5-SBU1-PadA8)") (class "Default")
      (node (ref "J5") (pin "A8") (pinfunction "SBU1_A8") (pintype "passive"))
    )
    (net (code "58") (name "unconnected-(J5-SBU2-PadB8)") (class "Default")
      (node (ref "J5") (pin "B8") (pinfunction "SBU2_B8") (pintype "passive"))
    )
    (net (code "59") (name "unconnected-(U2-~{CE}-Pad3)") (class "Default")
      (node (ref "U2") (pin "3") (pinfunction "~{CE}_3") (pintype "input+no_connect"))
    )
  )
)
